# LedDimming.net
KiCad netlist of a schematic drawn in Altium Designer
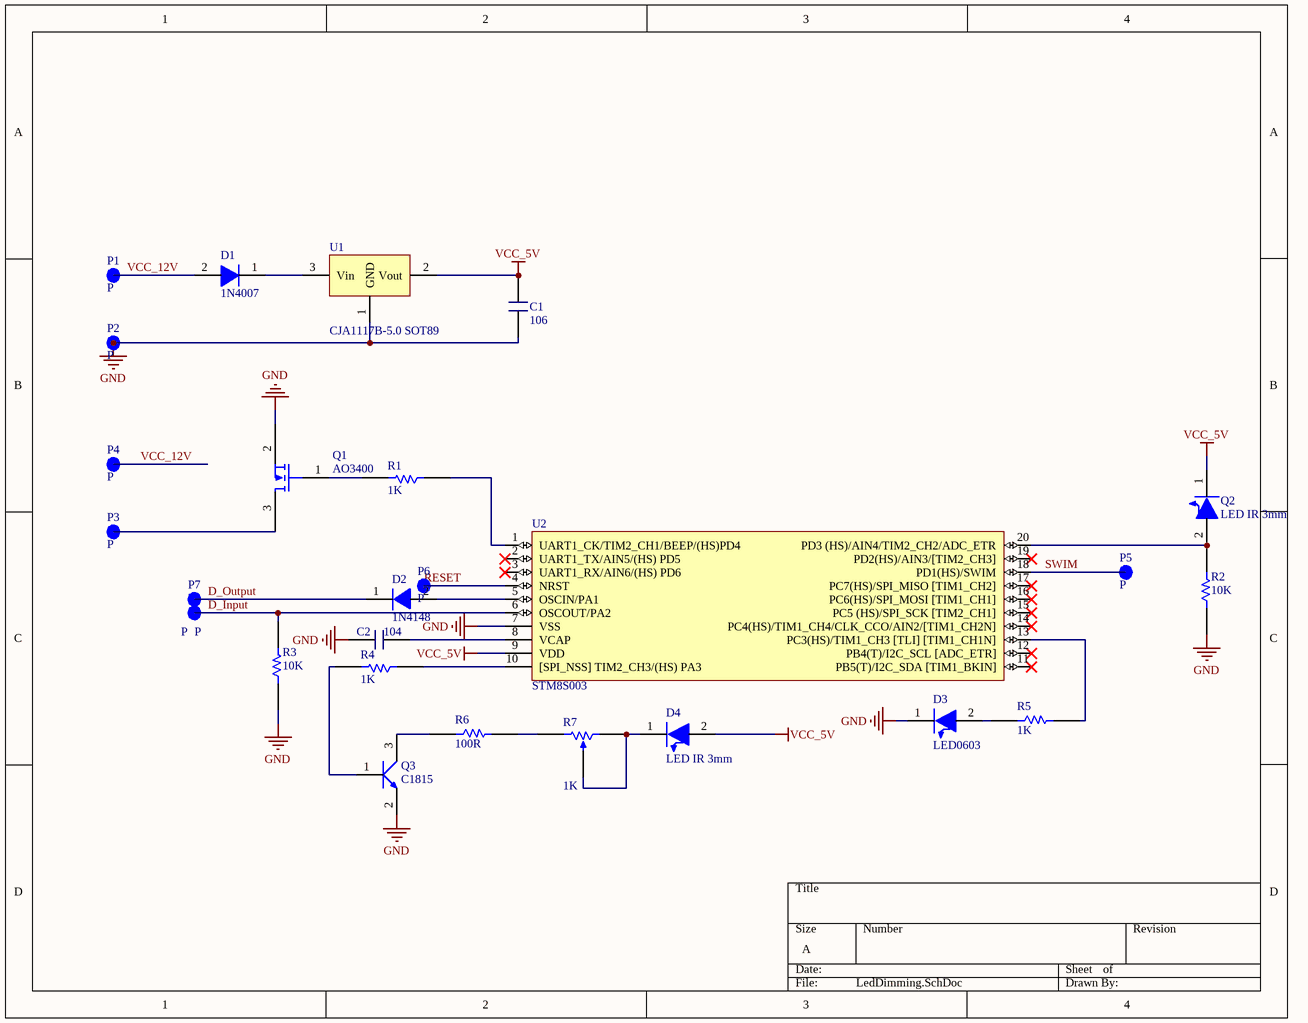
[diagram p0: LedDimming.SchDoc]

(export (version "E")
  (design (tool "Eeschema 10.0.6"))
  (components
    (comp (ref "C1")
      (value "106")
      (footprint "CAPC2012X12N")
      (libsource (lib "Integrated_Library1") (part "Capacitor 106"))
    )
    (comp (ref "C2")
      (value "104")
      (footprint "CAPC2012X12N")
      (libsource (lib "Integrated_Library1") (part "Capacitor 104 0603"))
    )
    (comp (ref "D1")
      (value "1N4007")
      (footprint "SODFL504X244-2N")
      (description "1N4007_SMD")
      (libsource (lib "Integrated_Library1") (part "1N4007_SMD Diode"))
    )
    (comp (ref "D2")
      (value "1N4148")
      (footprint "DIOMELF3515N")
      (description "DIODE GEN PURP 75V 200MA DO213AA")
      (libsource (lib "Integrated_Library1") (part "1N4148_SMD"))
    )
    (comp (ref "D3")
      (value "LED0603")
      (footprint "DIOC1608X06N")
      (libsource (lib "Integrated_Library1") (part "LED0603"))
    )
    (comp (ref "D4")
      (value "LED IR 3mm")
      (footprint "LED_IR_3mm")
      (libsource (lib "Integrated_Library1") (part "LED IR 3mm"))
    )
    (comp (ref "P1") (value "P") (footprint "Point") (libsource (lib "Integrated_Library1") (part "Point")))
    (comp (ref "P2") (value "P") (footprint "Point") (libsource (lib "Integrated_Library1") (part "Point")))
    (comp (ref "P3") (value "P") (footprint "Point") (libsource (lib "Integrated_Library1") (part "Point")))
    (comp (ref "P4") (value "P") (footprint "Point") (libsource (lib "Integrated_Library1") (part "Point")))
    (comp (ref "P5") (value "P") (footprint "Point") (libsource (lib "Integrated_Library1") (part "Point")))
    (comp (ref "P6") (value "P") (footprint "Point") (libsource (lib "Integrated_Library1") (part "Point")))
    (comp (ref "P7") (value "P") (footprint "Point") (libsource (lib "Integrated_Library1") (part "Point")))
    (comp (ref "P8") (value "P") (footprint "Point") (libsource (lib "Integrated_Library1") (part "Point")))
    (comp (ref "Q1")
      (value "AO3400")
      (footprint "SOT95P278X125-3N")
      (description "AO3400  MOSFET SOT23-3")
      (libsource (lib "Integrated_Library1") (part "AO3400  MOSFET SOT23-3"))
    )
    (comp (ref "Q2")
      (value "LED IR 3mm")
      (footprint "LED_IR_3mm")
      (libsource (lib "Integrated_Library1") (part "LED IR 3mm"))
    )
    (comp (ref "Q3")
      (value "C1815")
      (footprint "SOT95P278X125-3N")
      (description "SOT-23 Plastic-Encapsulate Transistors")
      (libsource (lib "Integrated_Library1") (part "Transitor C1815 NPN"))
    )
    (comp (ref "R1")
      (value "1K")
      (footprint "RESC2608X06N_0603")
      (description "Thick Film Resistors - SMD 0603 1kOHMS 5% 1/10WATT")
      (libsource (lib "Integrated_Library1") (part "1k_0603_5%"))
    )
    (comp (ref "R2")
      (value "10K")
      (footprint "RESC2608X06N_0603")
      (description "RES SMD 10K OHM 1% 1/4W 0603")
      (libsource (lib "Integrated_Library1") (part "R10k_0603_5%"))
    )
    (comp (ref "R3")
      (value "10K")
      (footprint "RESC2608X06N_0603")
      (description "RES SMD 10K OHM 1% 1/4W 0603")
      (libsource (lib "Integrated_Library1") (part "R10k_0603_5%"))
    )
    (comp (ref "R4")
      (value "1K")
      (footprint "RESC2608X06N_0603")
      (description "Thick Film Resistors - SMD 0603 1kOHMS 5% 1/10WATT")
      (libsource (lib "Integrated_Library1") (part "1k_0603_5%"))
    )
    (comp (ref "R5")
      (value "1K")
      (footprint "RESC2608X06N_0603")
      (description "Thick Film Resistors - SMD 0603 1kOHMS 5% 1/10WATT")
      (libsource (lib "Integrated_Library1") (part "1k_0603_5%"))
    )
    (comp (ref "R6")
      (value "100R")
      (footprint "RESC2608X06N_0603")
      (description "Thick Film Resistors - SMD 0603 100OHMS 5% 1/10WATT")
      (libsource (lib "Integrated_Library1") (part "R100_0603_5%"))
    )
    (comp (ref "R7")
      (value "1K")
      (footprint "Var_SMD_3x3")
      (description "Varistor 3x3 SMD 1KOhm 5% 1/10WATT")
      (libsource (lib "Integrated_Library1") (part "Varistor 3x3 SMD 1KOhm"))
    )
    (comp (ref "U1")
      (value "CJA1117B-5.0 SOT89")
      (footprint "SOT89-150P409X160-3N")
      (description "CJA1117B-5.0 SOT89 Power IC 1A 5V_IC")
      (libsource (lib "Integrated_Library1") (part "CJA1117B-5.0 SOT89"))
    )
    (comp (ref "U2")
      (value "STM8S003")
      (footprint "TSOP65P640X120-20N")
      (description "MCU 8-bit STM8S STM8 CISC 8KB Flash 3.3V/5V 20-Pin TSSOP T/R")
      (libsource (lib "Integrated_Library1") (part "STM8S003"))
    )
  )
  (nets
    (net (code "1") (name "/D_Input") (class "Default")
      (node (ref "P8") (pin "1") (pinfunction "1_1") (pintype "passive"))
      (node (ref "R3") (pin "2") (pinfunction "2_2") (pintype "passive"))
      (node (ref "U2") (pin "6") (pinfunction "OSCOUT/PA2_6") (pintype "bidirectional"))
    )
    (net (code "2") (name "/D_Output") (class "Default")
      (node (ref "D2") (pin "1") (pinfunction "C_1") (pintype "passive"))
      (node (ref "P7") (pin "1") (pinfunction "1_1") (pintype "passive"))
    )
    (net (code "3") (name "/RESET") (class "Default")
      (node (ref "P6") (pin "1") (pinfunction "1_1") (pintype "passive"))
      (node (ref "U2") (pin "4") (pinfunction "NRST_4") (pintype "bidirectional"))
    )
    (net (code "4") (name "/SWIM") (class "Default")
      (node (ref "P5") (pin "1") (pinfunction "1_1") (pintype "passive"))
      (node (ref "U2") (pin "18") (pinfunction "PD1(HS)/SWIM_18") (pintype "bidirectional"))
    )
    (net (code "5") (name "/VCC_12V") (class "Default")
      (node (ref "D1") (pin "2") (pinfunction "A_2") (pintype "passive"))
      (node (ref "P1") (pin "1") (pinfunction "1_1") (pintype "passive"))
      (node (ref "P4") (pin "1") (pinfunction "1_1") (pintype "passive"))
    )
    (net (code "6") (name "GND") (class "Default")
      (node (ref "C1") (pin "1") (pinfunction "1_1") (pintype "passive"))
      (node (ref "C2") (pin "1") (pinfunction "1_1") (pintype "passive"))
      (node (ref "D3") (pin "1") (pinfunction "A_1") (pintype "passive"))
      (node (ref "P2") (pin "1") (pinfunction "1_1") (pintype "passive"))
      (node (ref "Q1") (pin "2") (pinfunction "S_2") (pintype "passive"))
      (node (ref "Q3") (pin "2") (pinfunction "E_2") (pintype "passive"))
      (node (ref "R2") (pin "1") (pinfunction "1_1") (pintype "passive"))
      (node (ref "R3") (pin "1") (pinfunction "1_1") (pintype "passive"))
      (node (ref "U1") (pin "1") (pinfunction "GND_1") (pintype "power_in"))
      (node (ref "U2") (pin "7") (pinfunction "VSS_7") (pintype "power_in"))
    )
    (net (code "7") (name "Net-(D1-C)") (class "Default")
      (node (ref "D1") (pin "1") (pinfunction "C_1") (pintype "passive"))
      (node (ref "U1") (pin "3") (pinfunction "Vin_3") (pintype "power_in"))
    )
    (net (code "8") (name "Net-(D2-A)") (class "Default")
      (node (ref "D2") (pin "2") (pinfunction "A_2") (pintype "passive"))
      (node (ref "U2") (pin "5") (pinfunction "OSCIN/PA1_5") (pintype "bidirectional"))
    )
    (net (code "9") (name "Net-(D3-C)") (class "Default")
      (node (ref "D3") (pin "2") (pinfunction "C_2") (pintype "passive"))
      (node (ref "R5") (pin "1") (pinfunction "1_1") (pintype "passive"))
    )
    (net (code "10") (name "Net-(D4-A)") (class "Default")
      (node (ref "D4") (pin "1") (pinfunction "A_1") (pintype "passive"))
      (node (ref "R7") (pin "1") (pinfunction "1_1") (pintype "passive"))
      (node (ref "R7") (pin "2") (pinfunction "2_2") (pintype "passive"))
    )
    (net (code "11") (name "Net-(Q1-D)") (class "Default")
      (node (ref "P3") (pin "1") (pinfunction "1_1") (pintype "passive"))
      (node (ref "Q1") (pin "3") (pinfunction "D_3") (pintype "passive"))
    )
    (net (code "12") (name "Net-(Q1-G)") (class "Default")
      (node (ref "Q1") (pin "1") (pinfunction "G_1") (pintype "passive"))
      (node (ref "R1") (pin "2") (pinfunction "2_2") (pintype "passive"))
    )
    (net (code "13") (name "Net-(Q2-C)") (class "Default")
      (node (ref "Q2") (pin "2") (pinfunction "C_2") (pintype "passive"))
      (node (ref "R2") (pin "2") (pinfunction "2_2") (pintype "passive"))
      (node (ref "U2") (pin "20") (pinfunction "PD3_(HS)/AIN4/TIM2_CH2/ADC_ETR_20") (pintype "bidirectional"))
    )
    (net (code "14") (name "Net-(Q3-B)") (class "Default")
      (node (ref "Q3") (pin "1") (pinfunction "B_1") (pintype "passive"))
      (node (ref "R4") (pin "2") (pinfunction "2_2") (pintype "passive"))
    )
    (net (code "15") (name "Net-(Q3-C)") (class "Default")
      (node (ref "Q3") (pin "3") (pinfunction "C_3") (pintype "passive"))
      (node (ref "R6") (pin "1") (pinfunction "1_1") (pintype "passive"))
    )
    (net (code "16") (name "Net-(R6-Pad2)") (class "Default")
      (node (ref "R6") (pin "2") (pinfunction "2_2") (pintype "passive"))
      (node (ref "R7") (pin "3") (pinfunction "3_3") (pintype "passive"))
    )
    (net (code "17") (name "Net-(U2-PC3(HS){slash}TIM1_CH3_[TLI]_[TIM1_CH1N])") (class "Default")
      (node (ref "R5") (pin "2") (pinfunction "2_2") (pintype "passive"))
      (node (ref "U2") (pin "13") (pinfunction "PC3(HS)/TIM1_CH3_[TLI]_[TIM1_CH1N]_13") (pintype "bidirectional"))
    )
    (net (code "18") (name "Net-(U2-UART1_CK{slash}TIM2_CH1{slash}BEEP{slash}(HS)PD4)") (class "Default")
      (node (ref "R1") (pin "1") (pinfunction "1_1") (pintype "passive"))
      (node (ref "U2") (pin "1") (pinfunction "UART1_CK/TIM2_CH1/BEEP/(HS)PD4_1") (pintype "bidirectional"))
    )
    (net (code "19") (name "Net-(U2-VCAP)") (class "Default")
      (node (ref "C2") (pin "2") (pinfunction "2_2") (pintype "passive"))
      (node (ref "U2") (pin "8") (pinfunction "VCAP_8") (pintype "power_in"))
    )
    (net (code "20") (name "Net-(U2-[SPI_NSS]_TIM2_CH3{slash}(HS)_PA3)") (class "Default")
      (node (ref "R4") (pin "1") (pinfunction "1_1") (pintype "passive"))
      (node (ref "U2") (pin "10") (pinfunction "[SPI_NSS]_TIM2_CH3/(HS)_PA3_10") (pintype "power_in"))
    )
    (net (code "21") (name "VCC_5V") (class "Default")
      (node (ref "C1") (pin "2") (pinfunction "2_2") (pintype "passive"))
      (node (ref "D4") (pin "2") (pinfunction "C_2") (pintype "passive"))
      (node (ref "Q2") (pin "1") (pinfunction "A_1") (pintype "passive"))
      (node (ref "U1") (pin "2") (pinfunction "Vout_2") (pintype "power_in"))
      (node (ref "U2") (pin "9") (pinfunction "VDD_9") (pintype "power_in"))
    )
    (net (code "22") (name "unconnected-(U2-PB4(T){slash}I2C_SCL_[ADC_ETR]-Pad12)") (class "Default")
      (node (ref "U2") (pin "12") (pinfunction "PB4(T)/I2C_SCL_[ADC_ETR]_12") (pintype "bidirectional+no_connect"))
    )
    (net (code "23") (name "unconnected-(U2-PB5(T){slash}I2C_SDA_[TIM1_BKIN]-Pad11)") (class "Default")
      (node (ref "U2") (pin "11") (pinfunction "PB5(T)/I2C_SDA_[TIM1_BKIN]_11") (pintype "bidirectional+no_connect"))
    )
    (net (code "24") (name "unconnected-(U2-PC4(HS){slash}TIM1_CH4{slash}CLK_CCO{slash}AIN2{slash}[TIM1_CH2N]-Pad14)") (class "Default")
      (node (ref "U2") (pin "14") (pinfunction "PC4(HS)/TIM1_CH4/CLK_CCO/AIN2/[TIM1_CH2N]_14") (pintype "bidirectional+no_connect"))
    )
    (net (code "25") (name "unconnected-(U2-PC5_(HS){slash}SPI_SCK_[TIM2_CH1]-Pad15)") (class "Default")
      (node (ref "U2") (pin "15") (pinfunction "PC5_(HS)/SPI_SCK_[TIM2_CH1]_15") (pintype "bidirectional+no_connect"))
    )
    (net (code "26") (name "unconnected-(U2-PC6(HS){slash}SPI_MOSI_[TIM1_CH1]-Pad16)") (class "Default")
      (node (ref "U2") (pin "16") (pinfunction "PC6(HS)/SPI_MOSI_[TIM1_CH1]_16") (pintype "bidirectional+no_connect"))
    )
    (net (code "27") (name "unconnected-(U2-PC7(HS){slash}SPI_MISO_[TIM1_CH2]-Pad17)") (class "Default")
      (node (ref "U2") (pin "17") (pinfunction "PC7(HS)/SPI_MISO_[TIM1_CH2]_17") (pintype "bidirectional+no_connect"))
    )
    (net (code "28") (name "unconnected-(U2-PD2(HS){slash}AIN3{slash}[TIM2_CH3]-Pad19)") (class "Default")
      (node (ref "U2") (pin "19") (pinfunction "PD2(HS)/AIN3/[TIM2_CH3]_19") (pintype "bidirectional+no_connect"))
    )
    (net (code "29") (name "unconnected-(U2-UART1_RX{slash}AIN6{slash}(HS)_PD6-Pad3)") (class "Default")
      (node (ref "U2") (pin "3") (pinfunction "UART1_RX/AIN6/(HS)_PD6_3") (pintype "bidirectional+no_connect"))
    )
    (net (code "30") (name "unconnected-(U2-UART1_TX{slash}AIN5{slash}(HS)_PD5-Pad2)") (class "Default")
      (node (ref "U2") (pin "2") (pinfunction "UART1_TX/AIN5/(HS)_PD5_2") (pintype "bidirectional+no_connect"))
    )
  )
)
